# matrix.net
KiCad netlist of a schematic drawn in Altium Designer
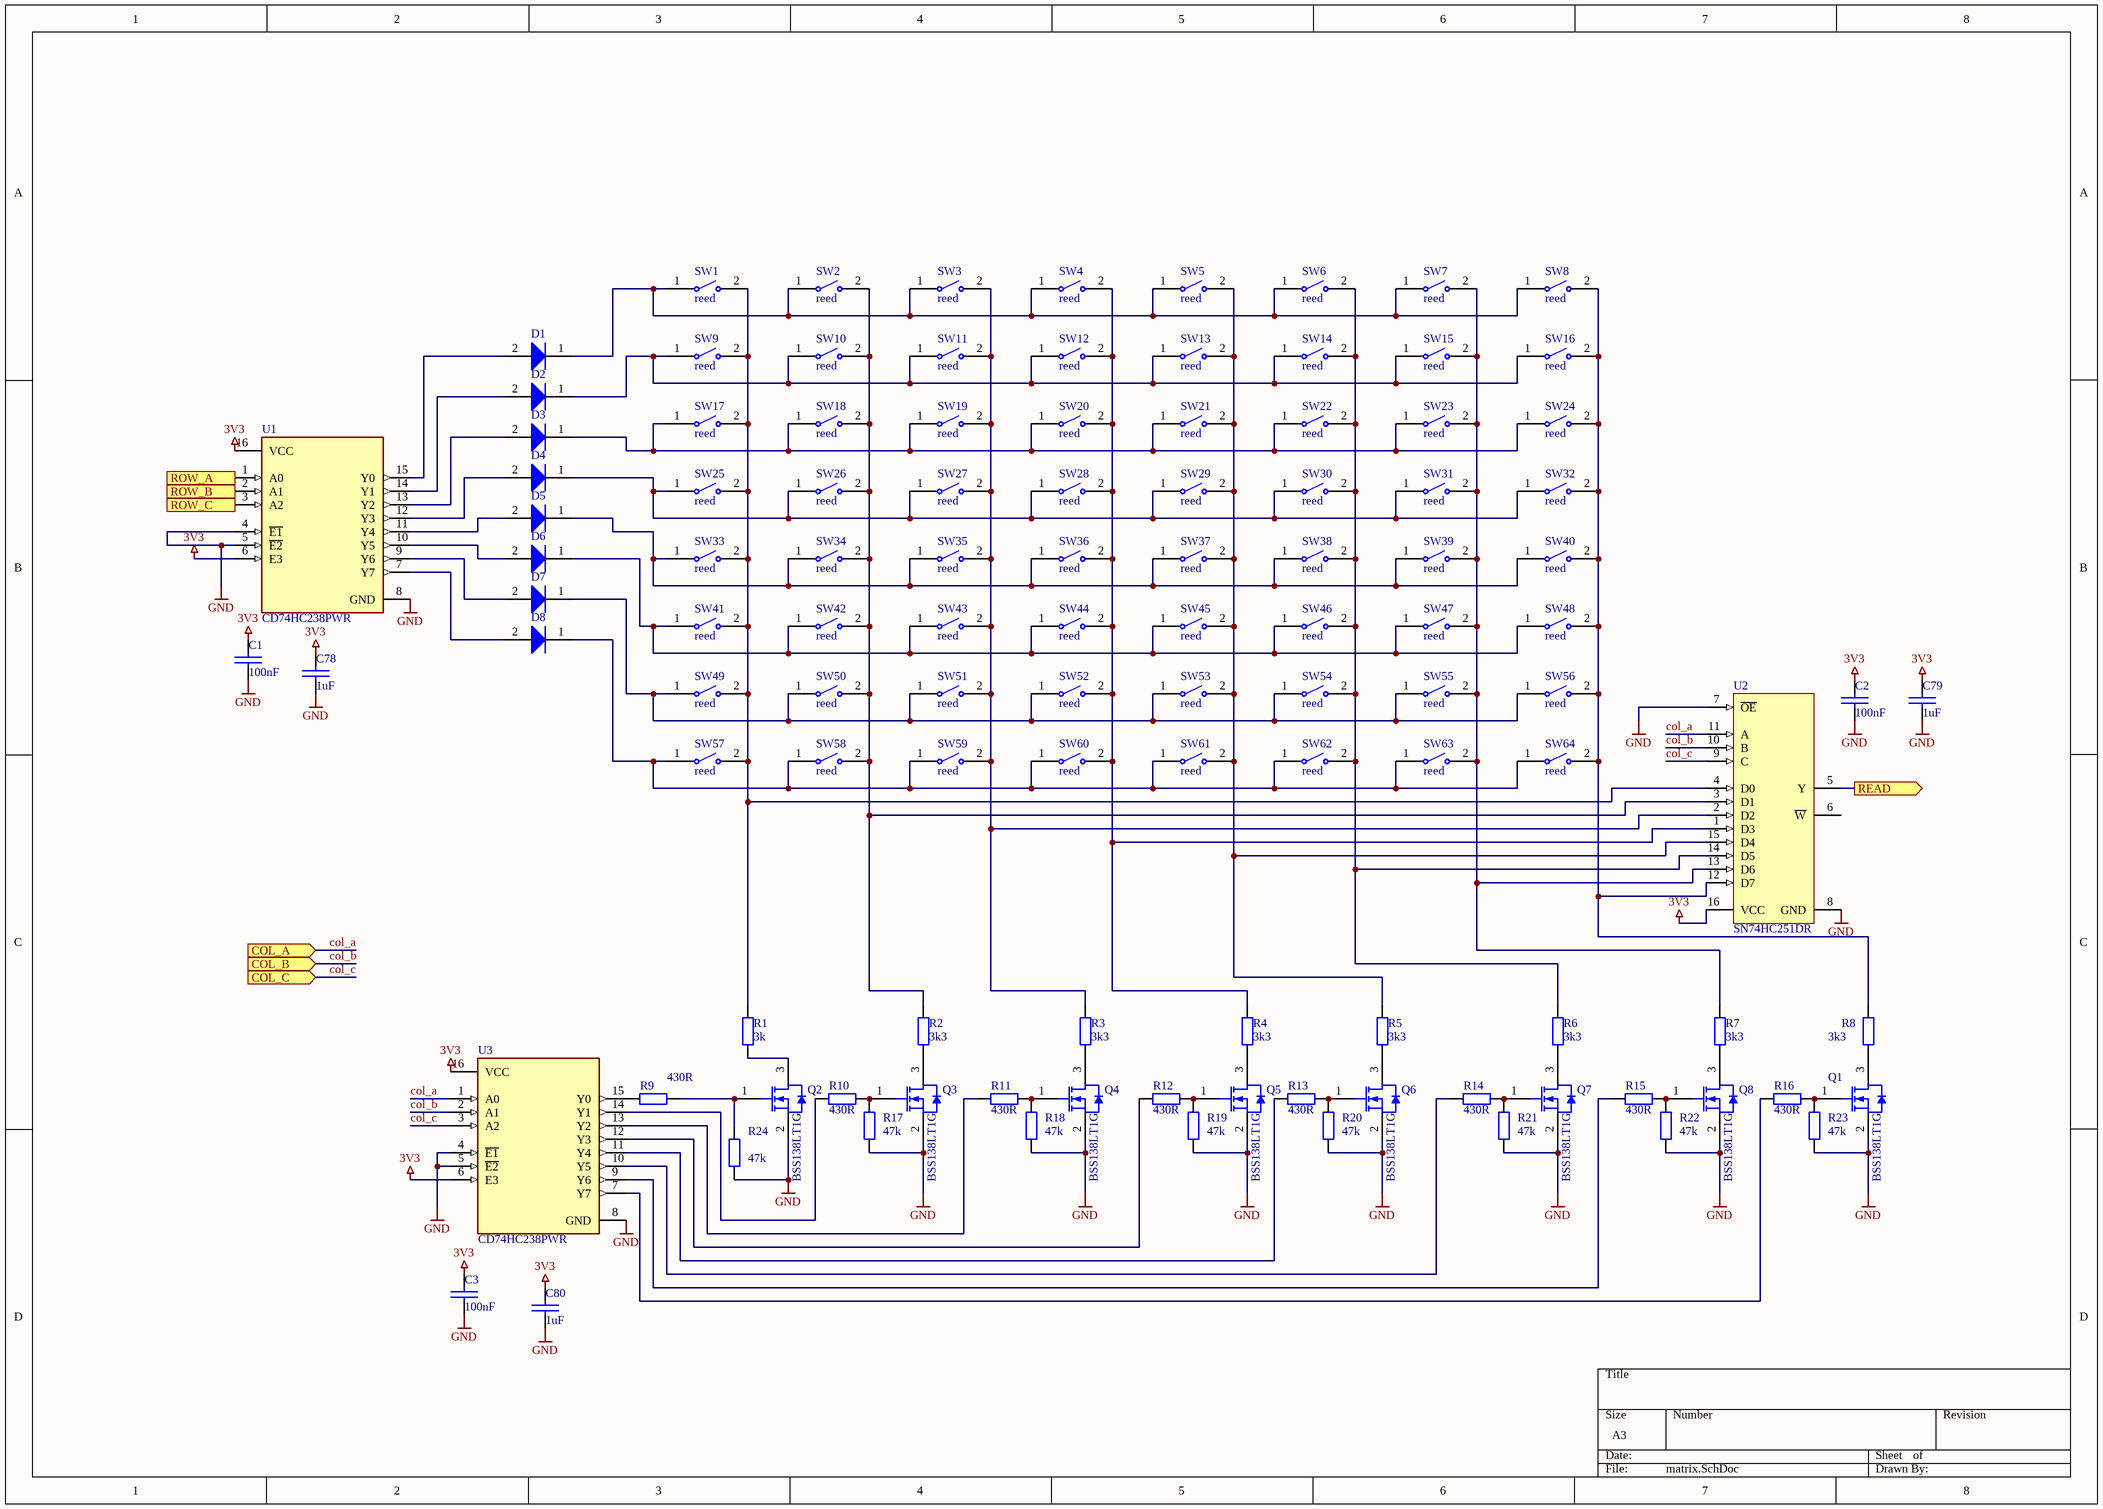
[diagram p0: matrix.SchDoc]

(export (version "E")
  (design (tool "Eeschema 10.0.6"))
  (components
    (comp (ref "C1") (value "100nF") (footprint "Cap_0805") (libsource (lib "*") (part "C")))
    (comp (ref "C2") (value "100nF") (footprint "Cap_0805") (libsource (lib "*") (part "C")))
    (comp (ref "C3") (value "100nF") (footprint "Cap_0805") (libsource (lib "*") (part "C")))
    (comp (ref "C78") (value "1uF") (footprint "Cap_0805") (libsource (lib "*") (part "C")))
    (comp (ref "C79") (value "1uF") (footprint "Cap_0805") (libsource (lib "*") (part "C")))
    (comp (ref "C80") (value "1uF") (footprint "Cap_0805") (libsource (lib "*") (part "C")))
    (comp (ref "D1")
      (value "BAT54HT1G")
      (footprint "ONSC-SOD-323-2-477-02_V")
      (description "Schottky Barrier Diode, 2-Pin SOD-323, Pb-Free, Tape and Reel")
      (fields (field (name "MANUFACTURER") "On Semiconductor"))
      (libsource (lib "Altium Content Vault") (part "ONSC-D-K1A2-2"))
    )
    (comp (ref "D2")
      (value "BAT54HT1G")
      (footprint "ONSC-SOD-323-2-477-02_V")
      (description "Schottky Barrier Diode, 2-Pin SOD-323, Pb-Free, Tape and Reel")
      (fields (field (name "MANUFACTURER") "On Semiconductor"))
      (libsource (lib "Altium Content Vault") (part "ONSC-D-K1A2-2"))
    )
    (comp (ref "D3")
      (value "BAT54HT1G")
      (footprint "ONSC-SOD-323-2-477-02_V")
      (description "Schottky Barrier Diode, 2-Pin SOD-323, Pb-Free, Tape and Reel")
      (fields (field (name "MANUFACTURER") "On Semiconductor"))
      (libsource (lib "Altium Content Vault") (part "ONSC-D-K1A2-2"))
    )
    (comp (ref "D4")
      (value "BAT54HT1G")
      (footprint "ONSC-SOD-323-2-477-02_V")
      (description "Schottky Barrier Diode, 2-Pin SOD-323, Pb-Free, Tape and Reel")
      (fields (field (name "MANUFACTURER") "On Semiconductor"))
      (libsource (lib "Altium Content Vault") (part "ONSC-D-K1A2-2"))
    )
    (comp (ref "D5")
      (value "BAT54HT1G")
      (footprint "ONSC-SOD-323-2-477-02_V")
      (description "Schottky Barrier Diode, 2-Pin SOD-323, Pb-Free, Tape and Reel")
      (fields (field (name "MANUFACTURER") "On Semiconductor"))
      (libsource (lib "Altium Content Vault") (part "ONSC-D-K1A2-2"))
    )
    (comp (ref "D6")
      (value "BAT54HT1G")
      (footprint "ONSC-SOD-323-2-477-02_V")
      (description "Schottky Barrier Diode, 2-Pin SOD-323, Pb-Free, Tape and Reel")
      (fields (field (name "MANUFACTURER") "On Semiconductor"))
      (libsource (lib "Altium Content Vault") (part "ONSC-D-K1A2-2"))
    )
    (comp (ref "D7")
      (value "BAT54HT1G")
      (footprint "ONSC-SOD-323-2-477-02_V")
      (description "Schottky Barrier Diode, 2-Pin SOD-323, Pb-Free, Tape and Reel")
      (fields (field (name "MANUFACTURER") "On Semiconductor"))
      (libsource (lib "Altium Content Vault") (part "ONSC-D-K1A2-2"))
    )
    (comp (ref "D8")
      (value "BAT54HT1G")
      (footprint "ONSC-SOD-323-2-477-02_V")
      (description "Schottky Barrier Diode, 2-Pin SOD-323, Pb-Free, Tape and Reel")
      (fields (field (name "MANUFACTURER") "On Semiconductor"))
      (libsource (lib "Altium Content Vault") (part "ONSC-D-K1A2-2"))
    )
    (comp (ref "Q1")
      (value "BSS138LT1G")
      (footprint "ONSC-SOT-23-3-318-08_V")
      (description "Power MOSFET, 200 mA, 50 V, N-Channel, 3-Pin SOT-23, Pb-Free, Tape and Reel")
      (fields (field (name "MANUFACTURER") "On Semiconductor"))
      (libsource (lib "Altium Content Vault") (part "ONSC-NMOS-G1S2D3-3"))
    )
    (comp (ref "Q2")
      (value "BSS138LT1G")
      (footprint "ONSC-SOT-23-3-318-08_V")
      (description "Power MOSFET, 200 mA, 50 V, N-Channel, 3-Pin SOT-23, Pb-Free, Tape and Reel")
      (fields (field (name "MANUFACTURER") "On Semiconductor"))
      (libsource (lib "Altium Content Vault") (part "ONSC-NMOS-G1S2D3-3"))
    )
    (comp (ref "Q3")
      (value "BSS138LT1G")
      (footprint "ONSC-SOT-23-3-318-08_V")
      (description "Power MOSFET, 200 mA, 50 V, N-Channel, 3-Pin SOT-23, Pb-Free, Tape and Reel")
      (fields (field (name "MANUFACTURER") "On Semiconductor"))
      (libsource (lib "Altium Content Vault") (part "ONSC-NMOS-G1S2D3-3"))
    )
    (comp (ref "Q4")
      (value "BSS138LT1G")
      (footprint "ONSC-SOT-23-3-318-08_V")
      (description "Power MOSFET, 200 mA, 50 V, N-Channel, 3-Pin SOT-23, Pb-Free, Tape and Reel")
      (fields (field (name "MANUFACTURER") "On Semiconductor"))
      (libsource (lib "Altium Content Vault") (part "ONSC-NMOS-G1S2D3-3"))
    )
    (comp (ref "Q5")
      (value "BSS138LT1G")
      (footprint "ONSC-SOT-23-3-318-08_V")
      (description "Power MOSFET, 200 mA, 50 V, N-Channel, 3-Pin SOT-23, Pb-Free, Tape and Reel")
      (fields (field (name "MANUFACTURER") "On Semiconductor"))
      (libsource (lib "Altium Content Vault") (part "ONSC-NMOS-G1S2D3-3"))
    )
    (comp (ref "Q6")
      (value "BSS138LT1G")
      (footprint "ONSC-SOT-23-3-318-08_V")
      (description "Power MOSFET, 200 mA, 50 V, N-Channel, 3-Pin SOT-23, Pb-Free, Tape and Reel")
      (fields (field (name "MANUFACTURER") "On Semiconductor"))
      (libsource (lib "Altium Content Vault") (part "ONSC-NMOS-G1S2D3-3"))
    )
    (comp (ref "Q7")
      (value "BSS138LT1G")
      (footprint "ONSC-SOT-23-3-318-08_V")
      (description "Power MOSFET, 200 mA, 50 V, N-Channel, 3-Pin SOT-23, Pb-Free, Tape and Reel")
      (fields (field (name "MANUFACTURER") "On Semiconductor"))
      (libsource (lib "Altium Content Vault") (part "ONSC-NMOS-G1S2D3-3"))
    )
    (comp (ref "Q8")
      (value "BSS138LT1G")
      (footprint "ONSC-SOT-23-3-318-08_V")
      (description "Power MOSFET, 200 mA, 50 V, N-Channel, 3-Pin SOT-23, Pb-Free, Tape and Reel")
      (fields (field (name "MANUFACTURER") "On Semiconductor"))
      (libsource (lib "Altium Content Vault") (part "ONSC-NMOS-G1S2D3-3"))
    )
    (comp (ref "R1")
      (value "3k")
      (footprint "RES_0805")
      (description "Res 0805")
      (fields (field (name "Comment") "430R") (field (name "PUBLISHER") "Altium Limited"))
      (libsource (lib "") (part "Res2_2"))
    )
    (comp (ref "R2")
      (value "3k3")
      (footprint "RES_0805")
      (description "Res 0805")
      (fields (field (name "Comment") "430R") (field (name "PUBLISHER") "Altium Limited"))
      (libsource (lib "") (part "Res2_2"))
    )
    (comp (ref "R3")
      (value "3k3")
      (footprint "RES_0805")
      (description "Res 0805")
      (fields (field (name "Comment") "430R") (field (name "PUBLISHER") "Altium Limited"))
      (libsource (lib "") (part "Res2_2"))
    )
    (comp (ref "R4")
      (value "3k3")
      (footprint "RES_0805")
      (description "Res 0805")
      (fields (field (name "Comment") "430R") (field (name "PUBLISHER") "Altium Limited"))
      (libsource (lib "") (part "Res2_2"))
    )
    (comp (ref "R5")
      (value "3k3")
      (footprint "RES_0805")
      (description "Res 0805")
      (fields (field (name "Comment") "430R") (field (name "PUBLISHER") "Altium Limited"))
      (libsource (lib "") (part "Res2_2"))
    )
    (comp (ref "R6")
      (value "3k3")
      (footprint "RES_0805")
      (description "Res 0805")
      (fields (field (name "Comment") "430R") (field (name "PUBLISHER") "Altium Limited"))
      (libsource (lib "") (part "Res2_2"))
    )
    (comp (ref "R7")
      (value "3k3")
      (footprint "RES_0805")
      (description "Res 0805")
      (fields (field (name "Comment") "430R") (field (name "PUBLISHER") "Altium Limited"))
      (libsource (lib "") (part "Res2_2"))
    )
    (comp (ref "R8")
      (value "3k3")
      (footprint "RES_0805")
      (description "Res 0805")
      (fields (field (name "Comment") "430R") (field (name "PUBLISHER") "Altium Limited"))
      (libsource (lib "") (part "Res2_2"))
    )
    (comp (ref "R9")
      (value "430R")
      (footprint "RES_0805")
      (description "Res 0805")
      (fields (field (name "PUBLISHER") "Altium Limited"))
      (libsource (lib "") (part "Res2_1"))
    )
    (comp (ref "R10")
      (value "430R")
      (footprint "RES_0805")
      (description "Res 0805")
      (fields (field (name "PUBLISHER") "Altium Limited"))
      (libsource (lib "") (part "Res2_1"))
    )
    (comp (ref "R11")
      (value "430R")
      (footprint "RES_0805")
      (description "Res 0805")
      (fields (field (name "PUBLISHER") "Altium Limited"))
      (libsource (lib "") (part "Res2_1"))
    )
    (comp (ref "R12")
      (value "430R")
      (footprint "RES_0805")
      (description "Res 0805")
      (fields (field (name "PUBLISHER") "Altium Limited"))
      (libsource (lib "") (part "Res2_1"))
    )
    (comp (ref "R13")
      (value "430R")
      (footprint "RES_0805")
      (description "Res 0805")
      (fields (field (name "PUBLISHER") "Altium Limited"))
      (libsource (lib "") (part "Res2_1"))
    )
    (comp (ref "R14")
      (value "430R")
      (footprint "RES_0805")
      (description "Res 0805")
      (fields (field (name "PUBLISHER") "Altium Limited"))
      (libsource (lib "") (part "Res2_1"))
    )
    (comp (ref "R15")
      (value "430R")
      (footprint "RES_0805")
      (description "Res 0805")
      (fields (field (name "PUBLISHER") "Altium Limited"))
      (libsource (lib "") (part "Res2_1"))
    )
    (comp (ref "R16")
      (value "430R")
      (footprint "RES_0805")
      (description "Res 0805")
      (fields (field (name "PUBLISHER") "Altium Limited"))
      (libsource (lib "") (part "Res2_1"))
    )
    (comp (ref "R17")
      (value "47k")
      (footprint "RES_0805")
      (description "Res 0805")
      (fields (field (name "Comment") "10k") (field (name "PUBLISHER") "Altium Limited"))
      (libsource (lib "Miscellaneous Devices") (part "Res2"))
    )
    (comp (ref "R18")
      (value "47k")
      (footprint "RES_0805")
      (description "Res 0805")
      (fields (field (name "Comment") "10k") (field (name "PUBLISHER") "Altium Limited"))
      (libsource (lib "Miscellaneous Devices") (part "Res2"))
    )
    (comp (ref "R19")
      (value "47k")
      (footprint "RES_0805")
      (description "Res 0805")
      (fields (field (name "Comment") "10k") (field (name "PUBLISHER") "Altium Limited"))
      (libsource (lib "Miscellaneous Devices") (part "Res2"))
    )
    (comp (ref "R20")
      (value "47k")
      (footprint "RES_0805")
      (description "Res 0805")
      (fields (field (name "Comment") "10k") (field (name "PUBLISHER") "Altium Limited"))
      (libsource (lib "Miscellaneous Devices") (part "Res2"))
    )
    (comp (ref "R21")
      (value "47k")
      (footprint "RES_0805")
      (description "Res 0805")
      (fields (field (name "Comment") "10k") (field (name "PUBLISHER") "Altium Limited"))
      (libsource (lib "Miscellaneous Devices") (part "Res2"))
    )
    (comp (ref "R22")
      (value "47k")
      (footprint "RES_0805")
      (description "Res 0805")
      (fields (field (name "Comment") "10k") (field (name "PUBLISHER") "Altium Limited"))
      (libsource (lib "Miscellaneous Devices") (part "Res2"))
    )
    (comp (ref "R23")
      (value "47k")
      (footprint "RES_0805")
      (description "Res 0805")
      (fields (field (name "Comment") "10k") (field (name "PUBLISHER") "Altium Limited"))
      (libsource (lib "Miscellaneous Devices") (part "Res2"))
    )
    (comp (ref "R24")
      (value "47k")
      (footprint "RES_0805")
      (description "Res 0805")
      (fields (field (name "Comment") "10k") (field (name "PUBLISHER") "Altium Limited"))
      (libsource (lib "Miscellaneous Devices") (part "Res2"))
    )
    (comp (ref "SW1") (value "reed") (footprint "reed") (libsource (lib "AZR-LIB") (part "reed")))
    (comp (ref "SW2") (value "reed") (footprint "reed") (libsource (lib "AZR-LIB") (part "reed")))
    (comp (ref "SW3") (value "reed") (footprint "reed") (libsource (lib "AZR-LIB") (part "reed")))
    (comp (ref "SW4") (value "reed") (footprint "reed") (libsource (lib "AZR-LIB") (part "reed")))
    (comp (ref "SW5") (value "reed") (footprint "reed") (libsource (lib "AZR-LIB") (part "reed")))
    (comp (ref "SW6") (value "reed") (footprint "reed") (libsource (lib "AZR-LIB") (part "reed")))
    (comp (ref "SW7") (value "reed") (footprint "reed") (libsource (lib "AZR-LIB") (part "reed")))
    (comp (ref "SW8") (value "reed") (footprint "reed") (libsource (lib "AZR-LIB") (part "reed")))
    (comp (ref "SW9") (value "reed") (footprint "reed") (libsource (lib "AZR-LIB") (part "reed")))
    (comp (ref "SW10") (value "reed") (footprint "reed") (libsource (lib "AZR-LIB") (part "reed")))
    (comp (ref "SW11") (value "reed") (footprint "reed") (libsource (lib "AZR-LIB") (part "reed")))
    (comp (ref "SW12") (value "reed") (footprint "reed") (libsource (lib "AZR-LIB") (part "reed")))
    (comp (ref "SW13") (value "reed") (footprint "reed") (libsource (lib "AZR-LIB") (part "reed")))
    (comp (ref "SW14") (value "reed") (footprint "reed") (libsource (lib "AZR-LIB") (part "reed")))
    (comp (ref "SW15") (value "reed") (footprint "reed") (libsource (lib "AZR-LIB") (part "reed")))
    (comp (ref "SW16") (value "reed") (footprint "reed") (libsource (lib "AZR-LIB") (part "reed")))
    (comp (ref "SW17") (value "reed") (footprint "reed") (libsource (lib "AZR-LIB") (part "reed")))
    (comp (ref "SW18") (value "reed") (footprint "reed") (libsource (lib "AZR-LIB") (part "reed")))
    (comp (ref "SW19") (value "reed") (footprint "reed") (libsource (lib "AZR-LIB") (part "reed")))
    (comp (ref "SW20") (value "reed") (footprint "reed") (libsource (lib "AZR-LIB") (part "reed")))
    (comp (ref "SW21") (value "reed") (footprint "reed") (libsource (lib "AZR-LIB") (part "reed")))
    (comp (ref "SW22") (value "reed") (footprint "reed") (libsource (lib "AZR-LIB") (part "reed")))
    (comp (ref "SW23") (value "reed") (footprint "reed") (libsource (lib "AZR-LIB") (part "reed")))
    (comp (ref "SW24") (value "reed") (footprint "reed") (libsource (lib "AZR-LIB") (part "reed")))
    (comp (ref "SW25") (value "reed") (footprint "reed") (libsource (lib "AZR-LIB") (part "reed")))
    (comp (ref "SW26") (value "reed") (footprint "reed") (libsource (lib "AZR-LIB") (part "reed")))
    (comp (ref "SW27") (value "reed") (footprint "reed") (libsource (lib "AZR-LIB") (part "reed")))
    (comp (ref "SW28") (value "reed") (footprint "reed") (libsource (lib "AZR-LIB") (part "reed")))
    (comp (ref "SW29") (value "reed") (footprint "reed") (libsource (lib "AZR-LIB") (part "reed")))
    (comp (ref "SW30") (value "reed") (footprint "reed") (libsource (lib "AZR-LIB") (part "reed")))
    (comp (ref "SW31") (value "reed") (footprint "reed") (libsource (lib "AZR-LIB") (part "reed")))
    (comp (ref "SW32") (value "reed") (footprint "reed") (libsource (lib "AZR-LIB") (part "reed")))
    (comp (ref "SW33") (value "reed") (footprint "reed") (libsource (lib "AZR-LIB") (part "reed")))
    (comp (ref "SW34") (value "reed") (footprint "reed") (libsource (lib "AZR-LIB") (part "reed")))
    (comp (ref "SW35") (value "reed") (footprint "reed") (libsource (lib "AZR-LIB") (part "reed")))
    (comp (ref "SW36") (value "reed") (footprint "reed") (libsource (lib "AZR-LIB") (part "reed")))
    (comp (ref "SW37") (value "reed") (footprint "reed") (libsource (lib "AZR-LIB") (part "reed")))
    (comp (ref "SW38") (value "reed") (footprint "reed") (libsource (lib "AZR-LIB") (part "reed")))
    (comp (ref "SW39") (value "reed") (footprint "reed") (libsource (lib "AZR-LIB") (part "reed")))
    (comp (ref "SW40") (value "reed") (footprint "reed") (libsource (lib "AZR-LIB") (part "reed")))
    (comp (ref "SW41") (value "reed") (footprint "reed") (libsource (lib "AZR-LIB") (part "reed")))
    (comp (ref "SW42") (value "reed") (footprint "reed") (libsource (lib "AZR-LIB") (part "reed")))
    (comp (ref "SW43") (value "reed") (footprint "reed") (libsource (lib "AZR-LIB") (part "reed")))
    (comp (ref "SW44") (value "reed") (footprint "reed") (libsource (lib "AZR-LIB") (part "reed")))
    (comp (ref "SW45") (value "reed") (footprint "reed") (libsource (lib "AZR-LIB") (part "reed")))
    (comp (ref "SW46") (value "reed") (footprint "reed") (libsource (lib "AZR-LIB") (part "reed")))
    (comp (ref "SW47") (value "reed") (footprint "reed") (libsource (lib "AZR-LIB") (part "reed")))
    (comp (ref "SW48") (value "reed") (footprint "reed") (libsource (lib "AZR-LIB") (part "reed")))
    (comp (ref "SW49") (value "reed") (footprint "reed") (libsource (lib "AZR-LIB") (part "reed")))
    (comp (ref "SW50") (value "reed") (footprint "reed") (libsource (lib "AZR-LIB") (part "reed")))
    (comp (ref "SW51") (value "reed") (footprint "reed") (libsource (lib "AZR-LIB") (part "reed")))
    (comp (ref "SW52") (value "reed") (footprint "reed") (libsource (lib "AZR-LIB") (part "reed")))
    (comp (ref "SW53") (value "reed") (footprint "reed") (libsource (lib "AZR-LIB") (part "reed")))
    (comp (ref "SW54") (value "reed") (footprint "reed") (libsource (lib "AZR-LIB") (part "reed")))
    (comp (ref "SW55") (value "reed") (footprint "reed") (libsource (lib "AZR-LIB") (part "reed")))
    (comp (ref "SW56") (value "reed") (footprint "reed") (libsource (lib "AZR-LIB") (part "reed")))
    (comp (ref "SW57") (value "reed") (footprint "reed") (libsource (lib "AZR-LIB") (part "reed")))
    (comp (ref "SW58") (value "reed") (footprint "reed") (libsource (lib "AZR-LIB") (part "reed")))
    (comp (ref "SW59") (value "reed") (footprint "reed") (libsource (lib "AZR-LIB") (part "reed")))
    (comp (ref "SW60") (value "reed") (footprint "reed") (libsource (lib "AZR-LIB") (part "reed")))
    (comp (ref "SW61") (value "reed") (footprint "reed") (libsource (lib "AZR-LIB") (part "reed")))
    (comp (ref "SW62") (value "reed") (footprint "reed") (libsource (lib "AZR-LIB") (part "reed")))
    (comp (ref "SW63") (value "reed") (footprint "reed") (libsource (lib "AZR-LIB") (part "reed")))
    (comp (ref "SW64") (value "reed") (footprint "reed") (libsource (lib "AZR-LIB") (part "reed")))
    (comp (ref "U1")
      (value "CD74HC238PWR")
      (footprint "FP-PW0016A-IPC_A")
      (description "IC DECODER/DEMUX 1X3:8 16TSSOP")
      (libsource (lib "Altium Content Vault") (part "f089b561ce8a4d050bfb0896b82f489"))
    )
    (comp (ref "U2")
      (value "SN74HC251DR")
      (footprint "D0016A_L")
      (description "Data Selectors/Multiplexers With 3-State Outputs, D0016A, LARGE T&R")
      (fields
        (field (name "MANUFACTURER") "Texas Instruments")
        (field (name "GENERIC PART NUMBER") "SN74HC251")
      )
      (libsource (lib "Altium Content Vault") (part "TI-SN54_74XXX251-16"))
    )
    (comp (ref "U3")
      (value "CD74HC238PWR")
      (footprint "FP-PW0016A-IPC_A")
      (description "IC DECODER/DEMUX 1X3:8 16TSSOP")
      (libsource (lib "Altium Content Vault") (part "f089b561ce8a4d050bfb0896b82f489"))
    )
  )
  (nets
    (net (code "1") (name "/READ") (class "Default")
      (node (ref "U2") (pin "5") (pinfunction "Y_5") (pintype "tri_state"))
    )
    (net (code "2") (name "/ROW_A") (class "Default")
      (node (ref "U1") (pin "1") (pinfunction "A0_1") (pintype "input"))
    )
    (net (code "3") (name "/ROW_B") (class "Default")
      (node (ref "U1") (pin "2") (pinfunction "A1_2") (pintype "input"))
    )
    (net (code "4") (name "/ROW_C") (class "Default")
      (node (ref "U1") (pin "3") (pinfunction "A2_3") (pintype "input"))
    )
    (net (code "5") (name "/col_a") (class "Default")
      (node (ref "U2") (pin "11") (pinfunction "A_11") (pintype "input"))
      (node (ref "U3") (pin "1") (pinfunction "A0_1") (pintype "input"))
    )
    (net (code "6") (name "/col_b") (class "Default")
      (node (ref "U2") (pin "10") (pinfunction "B_10") (pintype "input"))
      (node (ref "U3") (pin "2") (pinfunction "A1_2") (pintype "input"))
    )
    (net (code "7") (name "/col_c") (class "Default")
      (node (ref "U2") (pin "9") (pinfunction "C_9") (pintype "input"))
      (node (ref "U3") (pin "3") (pinfunction "A2_3") (pintype "input"))
    )
    (net (code "8") (name "3V3") (class "Default")
      (node (ref "C1") (pin "1") (pinfunction "1_1") (pintype "passive"))
      (node (ref "C2") (pin "1") (pinfunction "1_1") (pintype "passive"))
      (node (ref "C3") (pin "1") (pinfunction "1_1") (pintype "passive"))
      (node (ref "C78") (pin "1") (pinfunction "1_1") (pintype "passive"))
      (node (ref "C79") (pin "1") (pinfunction "1_1") (pintype "passive"))
      (node (ref "C80") (pin "1") (pinfunction "1_1") (pintype "passive"))
      (node (ref "U1") (pin "16") (pinfunction "VCC_16") (pintype "power_in"))
      (node (ref "U1") (pin "6") (pinfunction "E3_6") (pintype "input"))
      (node (ref "U2") (pin "16") (pinfunction "VCC_16") (pintype "power_in"))
      (node (ref "U3") (pin "16") (pinfunction "VCC_16") (pintype "power_in"))
      (node (ref "U3") (pin "6") (pinfunction "E3_6") (pintype "input"))
    )
    (net (code "9") (name "GND") (class "Default")
      (node (ref "C1") (pin "2") (pinfunction "2_2") (pintype "passive"))
      (node (ref "C2") (pin "2") (pinfunction "2_2") (pintype "passive"))
      (node (ref "C3") (pin "2") (pinfunction "2_2") (pintype "passive"))
      (node (ref "C78") (pin "2") (pinfunction "2_2") (pintype "passive"))
      (node (ref "C79") (pin "2") (pinfunction "2_2") (pintype "passive"))
      (node (ref "C80") (pin "2") (pinfunction "2_2") (pintype "passive"))
      (node (ref "Q1") (pin "2") (pinfunction "S_2") (pintype "passive"))
      (node (ref "Q2") (pin "2") (pinfunction "S_2") (pintype "passive"))
      (node (ref "Q3") (pin "2") (pinfunction "S_2") (pintype "passive"))
      (node (ref "Q4") (pin "2") (pinfunction "S_2") (pintype "passive"))
      (node (ref "Q5") (pin "2") (pinfunction "S_2") (pintype "passive"))
      (node (ref "Q6") (pin "2") (pinfunction "S_2") (pintype "passive"))
      (node (ref "Q7") (pin "2") (pinfunction "S_2") (pintype "passive"))
      (node (ref "Q8") (pin "2") (pinfunction "S_2") (pintype "passive"))
      (node (ref "R17") (pin "1") (pinfunction "1_1") (pintype "passive"))
      (node (ref "R18") (pin "1") (pinfunction "1_1") (pintype "passive"))
      (node (ref "R19") (pin "1") (pinfunction "1_1") (pintype "passive"))
      (node (ref "R20") (pin "1") (pinfunction "1_1") (pintype "passive"))
      (node (ref "R21") (pin "1") (pinfunction "1_1") (pintype "passive"))
      (node (ref "R22") (pin "1") (pinfunction "1_1") (pintype "passive"))
      (node (ref "R23") (pin "1") (pinfunction "1_1") (pintype "passive"))
      (node (ref "R24") (pin "1") (pinfunction "1_1") (pintype "passive"))
      (node (ref "U1") (pin "4") (pinfunction "~{E1}_4") (pintype "input"))
      (node (ref "U1") (pin "5") (pinfunction "~{E2}_5") (pintype "input"))
      (node (ref "U1") (pin "8") (pinfunction "GND_8") (pintype "power_in"))
      (node (ref "U2") (pin "7") (pinfunction "~{OE}_7") (pintype "input"))
      (node (ref "U2") (pin "8") (pinfunction "GND_8") (pintype "power_in"))
      (node (ref "U3") (pin "4") (pinfunction "~{E1}_4") (pintype "input"))
      (node (ref "U3") (pin "5") (pinfunction "~{E2}_5") (pintype "input"))
      (node (ref "U3") (pin "8") (pinfunction "GND_8") (pintype "power_in"))
    )
    (net (code "10") (name "Net-(D1-A)") (class "Default")
      (node (ref "D1") (pin "2") (pinfunction "A_2") (pintype "passive"))
      (node (ref "U1") (pin "15") (pinfunction "Y0_15") (pintype "output"))
    )
    (net (code "11") (name "Net-(D1-K)") (class "Default")
      (node (ref "D1") (pin "1") (pinfunction "K_1") (pintype "passive"))
      (node (ref "SW1") (pin "1") (pinfunction "1_1") (pintype "passive"))
      (node (ref "SW2") (pin "1") (pinfunction "1_1") (pintype "passive"))
      (node (ref "SW3") (pin "1") (pinfunction "1_1") (pintype "passive"))
      (node (ref "SW4") (pin "1") (pinfunction "1_1") (pintype "passive"))
      (node (ref "SW5") (pin "1") (pinfunction "1_1") (pintype "passive"))
      (node (ref "SW6") (pin "1") (pinfunction "1_1") (pintype "passive"))
      (node (ref "SW7") (pin "1") (pinfunction "1_1") (pintype "passive"))
      (node (ref "SW8") (pin "1") (pinfunction "1_1") (pintype "passive"))
    )
    (net (code "12") (name "Net-(D2-A)") (class "Default")
      (node (ref "D2") (pin "2") (pinfunction "A_2") (pintype "passive"))
      (node (ref "U1") (pin "14") (pinfunction "Y1_14") (pintype "output"))
    )
    (net (code "13") (name "Net-(D2-K)") (class "Default")
      (node (ref "D2") (pin "1") (pinfunction "K_1") (pintype "passive"))
      (node (ref "SW10") (pin "1") (pinfunction "1_1") (pintype "passive"))
      (node (ref "SW11") (pin "1") (pinfunction "1_1") (pintype "passive"))
      (node (ref "SW12") (pin "1") (pinfunction "1_1") (pintype "passive"))
      (node (ref "SW13") (pin "1") (pinfunction "1_1") (pintype "passive"))
      (node (ref "SW14") (pin "1") (pinfunction "1_1") (pintype "passive"))
      (node (ref "SW15") (pin "1") (pinfunction "1_1") (pintype "passive"))
      (node (ref "SW16") (pin "1") (pinfunction "1_1") (pintype "passive"))
      (node (ref "SW9") (pin "1") (pinfunction "1_1") (pintype "passive"))
    )
    (net (code "14") (name "Net-(D3-A)") (class "Default")
      (node (ref "D3") (pin "2") (pinfunction "A_2") (pintype "passive"))
      (node (ref "U1") (pin "13") (pinfunction "Y2_13") (pintype "output"))
    )
    (net (code "15") (name "Net-(D3-K)") (class "Default")
      (node (ref "D3") (pin "1") (pinfunction "K_1") (pintype "passive"))
      (node (ref "SW17") (pin "1") (pinfunction "1_1") (pintype "passive"))
      (node (ref "SW18") (pin "1") (pinfunction "1_1") (pintype "passive"))
      (node (ref "SW19") (pin "1") (pinfunction "1_1") (pintype "passive"))
      (node (ref "SW20") (pin "1") (pinfunction "1_1") (pintype "passive"))
      (node (ref "SW21") (pin "1") (pinfunction "1_1") (pintype "passive"))
      (node (ref "SW22") (pin "1") (pinfunction "1_1") (pintype "passive"))
      (node (ref "SW23") (pin "1") (pinfunction "1_1") (pintype "passive"))
      (node (ref "SW24") (pin "1") (pinfunction "1_1") (pintype "passive"))
    )
    (net (code "16") (name "Net-(D4-A)") (class "Default")
      (node (ref "D4") (pin "2") (pinfunction "A_2") (pintype "passive"))
      (node (ref "U1") (pin "12") (pinfunction "Y3_12") (pintype "output"))
    )
    (net (code "17") (name "Net-(D4-K)") (class "Default")
      (node (ref "D4") (pin "1") (pinfunction "K_1") (pintype "passive"))
      (node (ref "SW25") (pin "1") (pinfunction "1_1") (pintype "passive"))
      (node (ref "SW26") (pin "1") (pinfunction "1_1") (pintype "passive"))
      (node (ref "SW27") (pin "1") (pinfunction "1_1") (pintype "passive"))
      (node (ref "SW28") (pin "1") (pinfunction "1_1") (pintype "passive"))
      (node (ref "SW29") (pin "1") (pinfunction "1_1") (pintype "passive"))
      (node (ref "SW30") (pin "1") (pinfunction "1_1") (pintype "passive"))
      (node (ref "SW31") (pin "1") (pinfunction "1_1") (pintype "passive"))
      (node (ref "SW32") (pin "1") (pinfunction "1_1") (pintype "passive"))
    )
    (net (code "18") (name "Net-(D5-A)") (class "Default")
      (node (ref "D5") (pin "2") (pinfunction "A_2") (pintype "passive"))
      (node (ref "U1") (pin "11") (pinfunction "Y4_11") (pintype "output"))
    )
    (net (code "19") (name "Net-(D5-K)") (class "Default")
      (node (ref "D5") (pin "1") (pinfunction "K_1") (pintype "passive"))
      (node (ref "SW33") (pin "1") (pinfunction "1_1") (pintype "passive"))
      (node (ref "SW34") (pin "1") (pinfunction "1_1") (pintype "passive"))
      (node (ref "SW35") (pin "1") (pinfunction "1_1") (pintype "passive"))
      (node (ref "SW36") (pin "1") (pinfunction "1_1") (pintype "passive"))
      (node (ref "SW37") (pin "1") (pinfunction "1_1") (pintype "passive"))
      (node (ref "SW38") (pin "1") (pinfunction "1_1") (pintype "passive"))
      (node (ref "SW39") (pin "1") (pinfunction "1_1") (pintype "passive"))
      (node (ref "SW40") (pin "1") (pinfunction "1_1") (pintype "passive"))
    )
    (net (code "20") (name "Net-(D6-A)") (class "Default")
      (node (ref "D6") (pin "2") (pinfunction "A_2") (pintype "passive"))
      (node (ref "U1") (pin "10") (pinfunction "Y5_10") (pintype "output"))
    )
    (net (code "21") (name "Net-(D6-K)") (class "Default")
      (node (ref "D6") (pin "1") (pinfunction "K_1") (pintype "passive"))
      (node (ref "SW41") (pin "1") (pinfunction "1_1") (pintype "passive"))
      (node (ref "SW42") (pin "1") (pinfunction "1_1") (pintype "passive"))
      (node (ref "SW43") (pin "1") (pinfunction "1_1") (pintype "passive"))
      (node (ref "SW44") (pin "1") (pinfunction "1_1") (pintype "passive"))
      (node (ref "SW45") (pin "1") (pinfunction "1_1") (pintype "passive"))
      (node (ref "SW46") (pin "1") (pinfunction "1_1") (pintype "passive"))
      (node (ref "SW47") (pin "1") (pinfunction "1_1") (pintype "passive"))
      (node (ref "SW48") (pin "1") (pinfunction "1_1") (pintype "passive"))
    )
    (net (code "22") (name "Net-(D7-A)") (class "Default")
      (node (ref "D7") (pin "2") (pinfunction "A_2") (pintype "passive"))
      (node (ref "U1") (pin "9") (pinfunction "Y6_9") (pintype "output"))
    )
    (net (code "23") (name "Net-(D7-K)") (class "Default")
      (node (ref "D7") (pin "1") (pinfunction "K_1") (pintype "passive"))
      (node (ref "SW49") (pin "1") (pinfunction "1_1") (pintype "passive"))
      (node (ref "SW50") (pin "1") (pinfunction "1_1") (pintype "passive"))
      (node (ref "SW51") (pin "1") (pinfunction "1_1") (pintype "passive"))
      (node (ref "SW52") (pin "1") (pinfunction "1_1") (pintype "passive"))
      (node (ref "SW53") (pin "1") (pinfunction "1_1") (pintype "passive"))
      (node (ref "SW54") (pin "1") (pinfunction "1_1") (pintype "passive"))
      (node (ref "SW55") (pin "1") (pinfunction "1_1") (pintype "passive"))
      (node (ref "SW56") (pin "1") (pinfunction "1_1") (pintype "passive"))
    )
    (net (code "24") (name "Net-(D8-A)") (class "Default")
      (node (ref "D8") (pin "2") (pinfunction "A_2") (pintype "passive"))
      (node (ref "U1") (pin "7") (pinfunction "Y7_7") (pintype "output"))
    )
    (net (code "25") (name "Net-(D8-K)") (class "Default")
      (node (ref "D8") (pin "1") (pinfunction "K_1") (pintype "passive"))
      (node (ref "SW57") (pin "1") (pinfunction "1_1") (pintype "passive"))
      (node (ref "SW58") (pin "1") (pinfunction "1_1") (pintype "passive"))
      (node (ref "SW59") (pin "1") (pinfunction "1_1") (pintype "passive"))
      (node (ref "SW60") (pin "1") (pinfunction "1_1") (pintype "passive"))
      (node (ref "SW61") (pin "1") (pinfunction "1_1") (pintype "passive"))
      (node (ref "SW62") (pin "1") (pinfunction "1_1") (pintype "passive"))
      (node (ref "SW63") (pin "1") (pinfunction "1_1") (pintype "passive"))
      (node (ref "SW64") (pin "1") (pinfunction "1_1") (pintype "passive"))
    )
    (net (code "26") (name "Net-(Q1-D)") (class "Default")
      (node (ref "Q1") (pin "3") (pinfunction "D_3") (pintype "passive"))
      (node (ref "R8") (pin "2") (pinfunction "2_2") (pintype "passive"))
    )
    (net (code "27") (name "Net-(Q1-G)") (class "Default")
      (node (ref "Q1") (pin "1") (pinfunction "G_1") (pintype "passive"))
      (node (ref "R16") (pin "1") (pinfunction "1_1") (pintype "passive"))
      (node (ref "R23") (pin "2") (pinfunction "2_2") (pintype "passive"))
    )
    (net (code "28") (name "Net-(Q2-D)") (class "Default")
      (node (ref "Q2") (pin "3") (pinfunction "D_3") (pintype "passive"))
      (node (ref "R1") (pin "2") (pinfunction "2_2") (pintype "passive"))
    )
    (net (code "29") (name "Net-(Q2-G)") (class "Default")
      (node (ref "Q2") (pin "1") (pinfunction "G_1") (pintype "passive"))
      (node (ref "R24") (pin "2") (pinfunction "2_2") (pintype "passive"))
      (node (ref "R9") (pin "1") (pinfunction "1_1") (pintype "passive"))
    )
    (net (code "30") (name "Net-(Q3-D)") (class "Default")
      (node (ref "Q3") (pin "3") (pinfunction "D_3") (pintype "passive"))
      (node (ref "R2") (pin "2") (pinfunction "2_2") (pintype "passive"))
    )
    (net (code "31") (name "Net-(Q3-G)") (class "Default")
      (node (ref "Q3") (pin "1") (pinfunction "G_1") (pintype "passive"))
      (node (ref "R10") (pin "1") (pinfunction "1_1") (pintype "passive"))
      (node (ref "R17") (pin "2") (pinfunction "2_2") (pintype "passive"))
    )
    (net (code "32") (name "Net-(Q4-D)") (class "Default")
      (node (ref "Q4") (pin "3") (pinfunction "D_3") (pintype "passive"))
      (node (ref "R3") (pin "2") (pinfunction "2_2") (pintype "passive"))
    )
    (net (code "33") (name "Net-(Q4-G)") (class "Default")
      (node (ref "Q4") (pin "1") (pinfunction "G_1") (pintype "passive"))
      (node (ref "R11") (pin "1") (pinfunction "1_1") (pintype "passive"))
      (node (ref "R18") (pin "2") (pinfunction "2_2") (pintype "passive"))
    )
    (net (code "34") (name "Net-(Q5-D)") (class "Default")
      (node (ref "Q5") (pin "3") (pinfunction "D_3") (pintype "passive"))
      (node (ref "R4") (pin "2") (pinfunction "2_2") (pintype "passive"))
    )
    (net (code "35") (name "Net-(Q5-G)") (class "Default")
      (node (ref "Q5") (pin "1") (pinfunction "G_1") (pintype "passive"))
      (node (ref "R12") (pin "1") (pinfunction "1_1") (pintype "passive"))
      (node (ref "R19") (pin "2") (pinfunction "2_2") (pintype "passive"))
    )
    (net (code "36") (name "Net-(Q6-D)") (class "Default")
      (node (ref "Q6") (pin "3") (pinfunction "D_3") (pintype "passive"))
      (node (ref "R5") (pin "2") (pinfunction "2_2") (pintype "passive"))
    )
    (net (code "37") (name "Net-(Q6-G)") (class "Default")
      (node (ref "Q6") (pin "1") (pinfunction "G_1") (pintype "passive"))
      (node (ref "R13") (pin "1") (pinfunction "1_1") (pintype "passive"))
      (node (ref "R20") (pin "2") (pinfunction "2_2") (pintype "passive"))
    )
    (net (code "38") (name "Net-(Q7-D)") (class "Default")
      (node (ref "Q7") (pin "3") (pinfunction "D_3") (pintype "passive"))
      (node (ref "R6") (pin "2") (pinfunction "2_2") (pintype "passive"))
    )
    (net (code "39") (name "Net-(Q7-G)") (class "Default")
      (node (ref "Q7") (pin "1") (pinfunction "G_1") (pintype "passive"))
      (node (ref "R14") (pin "1") (pinfunction "1_1") (pintype "passive"))
      (node (ref "R21") (pin "2") (pinfunction "2_2") (pintype "passive"))
    )
    (net (code "40") (name "Net-(Q8-D)") (class "Default")
      (node (ref "Q8") (pin "3") (pinfunction "D_3") (pintype "passive"))
      (node (ref "R7") (pin "2") (pinfunction "2_2") (pintype "passive"))
    )
    (net (code "41") (name "Net-(Q8-G)") (class "Default")
      (node (ref "Q8") (pin "1") (pinfunction "G_1") (pintype "passive"))
      (node (ref "R15") (pin "1") (pinfunction "1_1") (pintype "passive"))
      (node (ref "R22") (pin "2") (pinfunction "2_2") (pintype "passive"))
    )
    (net (code "42") (name "Net-(U2-D0)") (class "Default")
      (node (ref "R1") (pin "1") (pinfunction "1_1") (pintype "passive"))
      (node (ref "SW1") (pin "2") (pinfunction "2_2") (pintype "passive"))
      (node (ref "SW17") (pin "2") (pinfunction "2_2") (pintype "passive"))
      (node (ref "SW25") (pin "2") (pinfunction "2_2") (pintype "passive"))
      (node (ref "SW33") (pin "2") (pinfunction "2_2") (pintype "passive"))
      (node (ref "SW41") (pin "2") (pinfunction "2_2") (pintype "passive"))
      (node (ref "SW49") (pin "2") (pinfunction "2_2") (pintype "passive"))
      (node (ref "SW57") (pin "2") (pinfunction "2_2") (pintype "passive"))
      (node (ref "SW9") (pin "2") (pinfunction "2_2") (pintype "passive"))
      (node (ref "U2") (pin "4") (pinfunction "D0_4") (pintype "input"))
    )
    (net (code "43") (name "Net-(U2-D1)") (class "Default")
      (node (ref "R2") (pin "1") (pinfunction "1_1") (pintype "passive"))
      (node (ref "SW10") (pin "2") (pinfunction "2_2") (pintype "passive"))
      (node (ref "SW18") (pin "2") (pinfunction "2_2") (pintype "passive"))
      (node (ref "SW2") (pin "2") (pinfunction "2_2") (pintype "passive"))
      (node (ref "SW26") (pin "2") (pinfunction "2_2") (pintype "passive"))
      (node (ref "SW34") (pin "2") (pinfunction "2_2") (pintype "passive"))
      (node (ref "SW42") (pin "2") (pinfunction "2_2") (pintype "passive"))
      (node (ref "SW50") (pin "2") (pinfunction "2_2") (pintype "passive"))
      (node (ref "SW58") (pin "2") (pinfunction "2_2") (pintype "passive"))
      (node (ref "U2") (pin "3") (pinfunction "D1_3") (pintype "input"))
    )
    (net (code "44") (name "Net-(U2-D2)") (class "Default")
      (node (ref "R3") (pin "1") (pinfunction "1_1") (pintype "passive"))
      (node (ref "SW11") (pin "2") (pinfunction "2_2") (pintype "passive"))
      (node (ref "SW19") (pin "2") (pinfunction "2_2") (pintype "passive"))
      (node (ref "SW27") (pin "2") (pinfunction "2_2") (pintype "passive"))
      (node (ref "SW3") (pin "2") (pinfunction "2_2") (pintype "passive"))
      (node (ref "SW35") (pin "2") (pinfunction "2_2") (pintype "passive"))
      (node (ref "SW43") (pin "2") (pinfunction "2_2") (pintype "passive"))
      (node (ref "SW51") (pin "2") (pinfunction "2_2") (pintype "passive"))
      (node (ref "SW59") (pin "2") (pinfunction "2_2") (pintype "passive"))
      (node (ref "U2") (pin "2") (pinfunction "D2_2") (pintype "input"))
    )
    (net (code "45") (name "Net-(U2-D3)") (class "Default")
      (node (ref "R4") (pin "1") (pinfunction "1_1") (pintype "passive"))
      (node (ref "SW12") (pin "2") (pinfunction "2_2") (pintype "passive"))
      (node (ref "SW20") (pin "2") (pinfunction "2_2") (pintype "passive"))
      (node (ref "SW28") (pin "2") (pinfunction "2_2") (pintype "passive"))
      (node (ref "SW36") (pin "2") (pinfunction "2_2") (pintype "passive"))
      (node (ref "SW4") (pin "2") (pinfunction "2_2") (pintype "passive"))
      (node (ref "SW44") (pin "2") (pinfunction "2_2") (pintype "passive"))
      (node (ref "SW52") (pin "2") (pinfunction "2_2") (pintype "passive"))
      (node (ref "SW60") (pin "2") (pinfunction "2_2") (pintype "passive"))
      (node (ref "U2") (pin "1") (pinfunction "D3_1") (pintype "input"))
    )
    (net (code "46") (name "Net-(U2-D4)") (class "Default")
      (node (ref "R5") (pin "1") (pinfunction "1_1") (pintype "passive"))
      (node (ref "SW13") (pin "2") (pinfunction "2_2") (pintype "passive"))
      (node (ref "SW21") (pin "2") (pinfunction "2_2") (pintype "passive"))
      (node (ref "SW29") (pin "2") (pinfunction "2_2") (pintype "passive"))
      (node (ref "SW37") (pin "2") (pinfunction "2_2") (pintype "passive"))
      (node (ref "SW45") (pin "2") (pinfunction "2_2") (pintype "passive"))
      (node (ref "SW5") (pin "2") (pinfunction "2_2") (pintype "passive"))
      (node (ref "SW53") (pin "2") (pinfunction "2_2") (pintype "passive"))
      (node (ref "SW61") (pin "2") (pinfunction "2_2") (pintype "passive"))
      (node (ref "U2") (pin "15") (pinfunction "D4_15") (pintype "input"))
    )
    (net (code "47") (name "Net-(U2-D5)") (class "Default")
      (node (ref "R6") (pin "1") (pinfunction "1_1") (pintype "passive"))
      (node (ref "SW14") (pin "2") (pinfunction "2_2") (pintype "passive"))
      (node (ref "SW22") (pin "2") (pinfunction "2_2") (pintype "passive"))
      (node (ref "SW30") (pin "2") (pinfunction "2_2") (pintype "passive"))
      (node (ref "SW38") (pin "2") (pinfunction "2_2") (pintype "passive"))
      (node (ref "SW46") (pin "2") (pinfunction "2_2") (pintype "passive"))
      (node (ref "SW54") (pin "2") (pinfunction "2_2") (pintype "passive"))
      (node (ref "SW6") (pin "2") (pinfunction "2_2") (pintype "passive"))
      (node (ref "SW62") (pin "2") (pinfunction "2_2") (pintype "passive"))
      (node (ref "U2") (pin "14") (pinfunction "D5_14") (pintype "input"))
    )
    (net (code "48") (name "Net-(U2-D6)") (class "Default")
      (node (ref "R7") (pin "1") (pinfunction "1_1") (pintype "passive"))
      (node (ref "SW15") (pin "2") (pinfunction "2_2") (pintype "passive"))
      (node (ref "SW23") (pin "2") (pinfunction "2_2") (pintype "passive"))
      (node (ref "SW31") (pin "2") (pinfunction "2_2") (pintype "passive"))
      (node (ref "SW39") (pin "2") (pinfunction "2_2") (pintype "passive"))
      (node (ref "SW47") (pin "2") (pinfunction "2_2") (pintype "passive"))
      (node (ref "SW55") (pin "2") (pinfunction "2_2") (pintype "passive"))
      (node (ref "SW63") (pin "2") (pinfunction "2_2") (pintype "passive"))
      (node (ref "SW7") (pin "2") (pinfunction "2_2") (pintype "passive"))
      (node (ref "U2") (pin "13") (pinfunction "D6_13") (pintype "input"))
    )
    (net (code "49") (name "Net-(U2-D7)") (class "Default")
      (node (ref "R8") (pin "1") (pinfunction "1_1") (pintype "passive"))
      (node (ref "SW16") (pin "2") (pinfunction "2_2") (pintype "passive"))
      (node (ref "SW24") (pin "2") (pinfunction "2_2") (pintype "passive"))
      (node (ref "SW32") (pin "2") (pinfunction "2_2") (pintype "passive"))
      (node (ref "SW40") (pin "2") (pinfunction "2_2") (pintype "passive"))
      (node (ref "SW48") (pin "2") (pinfunction "2_2") (pintype "passive"))
      (node (ref "SW56") (pin "2") (pinfunction "2_2") (pintype "passive"))
      (node (ref "SW64") (pin "2") (pinfunction "2_2") (pintype "passive"))
      (node (ref "SW8") (pin "2") (pinfunction "2_2") (pintype "passive"))
      (node (ref "U2") (pin "12") (pinfunction "D7_12") (pintype "input"))
    )
    (net (code "50") (name "Net-(U3-Y0)") (class "Default")
      (node (ref "R9") (pin "2") (pinfunction "2_2") (pintype "passive"))
      (node (ref "U3") (pin "15") (pinfunction "Y0_15") (pintype "output"))
    )
    (net (code "51") (name "Net-(U3-Y1)") (class "Default")
      (node (ref "R10") (pin "2") (pinfunction "2_2") (pintype "passive"))
      (node (ref "U3") (pin "14") (pinfunction "Y1_14") (pintype "output"))
    )
    (net (code "52") (name "Net-(U3-Y2)") (class "Default")
      (node (ref "R11") (pin "2") (pinfunction "2_2") (pintype "passive"))
      (node (ref "U3") (pin "13") (pinfunction "Y2_13") (pintype "output"))
    )
    (net (code "53") (name "Net-(U3-Y3)") (class "Default")
      (node (ref "R12") (pin "2") (pinfunction "2_2") (pintype "passive"))
      (node (ref "U3") (pin "12") (pinfunction "Y3_12") (pintype "output"))
    )
    (net (code "54") (name "Net-(U3-Y4)") (class "Default")
      (node (ref "R13") (pin "2") (pinfunction "2_2") (pintype "passive"))
      (node (ref "U3") (pin "11") (pinfunction "Y4_11") (pintype "output"))
    )
    (net (code "55") (name "Net-(U3-Y5)") (class "Default")
      (node (ref "R14") (pin "2") (pinfunction "2_2") (pintype "passive"))
      (node (ref "U3") (pin "10") (pinfunction "Y5_10") (pintype "output"))
    )
    (net (code "56") (name "Net-(U3-Y6)") (class "Default")
      (node (ref "R15") (pin "2") (pinfunction "2_2") (pintype "passive"))
      (node (ref "U3") (pin "9") (pinfunction "Y6_9") (pintype "output"))
    )
    (net (code "57") (name "Net-(U3-Y7)") (class "Default")
      (node (ref "R16") (pin "2") (pinfunction "2_2") (pintype "passive"))
      (node (ref "U3") (pin "7") (pinfunction "Y7_7") (pintype "output"))
    )
    (net (code "58") (name "unconnected-(U2-~{W}-Pad6)") (class "Default")
      (node (ref "U2") (pin "6") (pinfunction "~{W}_6") (pintype "tri_state"))
    )
  )
)
